# USB_OTG_FS.net
KiCad netlist of a schematic drawn in Altium Designer
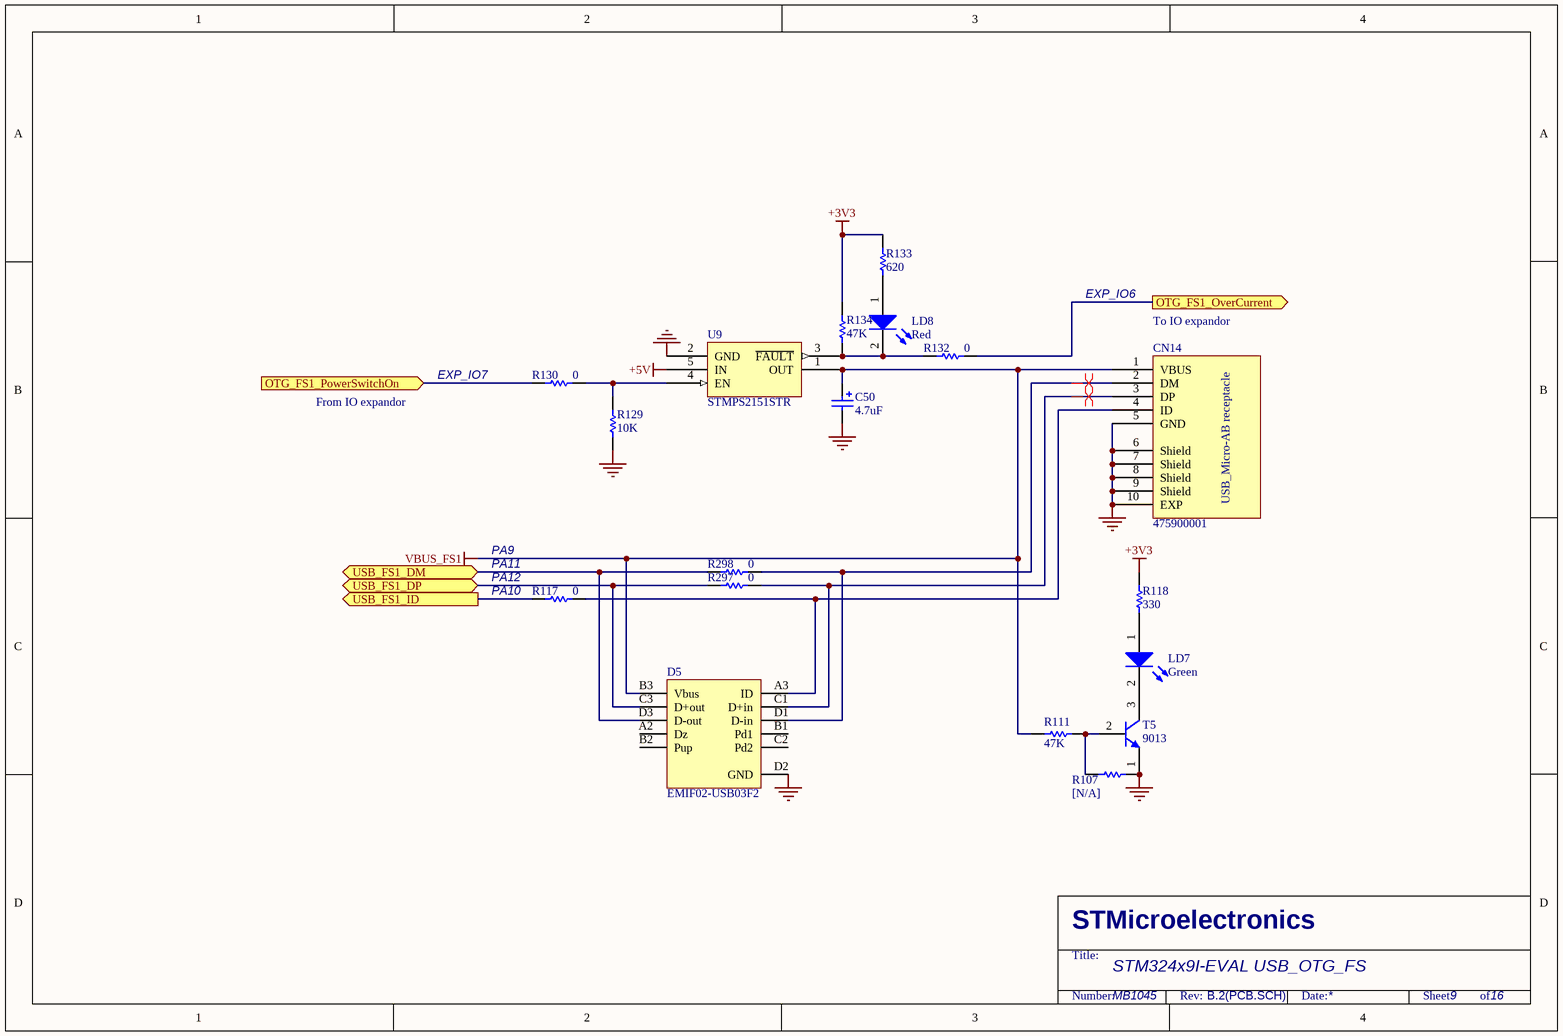
[diagram p0: USB_OTG_FS.SchDoc]

(export (version "E")
  (design (tool "Eeschema 10.0.6"))
  (components
    (comp (ref "C50")
      (value "4.7uF")
      (footprint "TAN-A")
      (description "Polarized Capacitor (Radial)")
      (fields (field (name "PUBLISHER") "Altium Limited"))
      (libsource (lib "Miscellaneous Devices") (part "Cap Pol1"))
    )
    (comp (ref "CN14")
      (value "475900001")
      (footprint "MOLEX_47590001")
      (libsource (lib "mb1045") (part "475900001"))
    )
    (comp (ref "D5")
      (value "EMIF02-USB03F2")
      (footprint "BGA11_0R5_1R57X2R07")
      (libsource (lib "mb1045") (part "EMIF02-USB03F2"))
    )
    (comp (ref "LD7")
      (value "Green")
      (footprint "0603D")
      (description "Typical RED, GREEN, YELLOW, AMBER GaAs LED")
      (fields (field (name "PUBLISHER") "Altium Limited"))
      (libsource (lib "Miscellaneous Devices") (part "LED2"))
    )
    (comp (ref "LD8")
      (value "Red")
      (footprint "0603D")
      (description "Typical RED, GREEN, YELLOW, AMBER GaAs LED")
      (fields (field (name "PUBLISHER") "Altium Limited"))
      (libsource (lib "Miscellaneous Devices") (part "LED2"))
    )
    (comp (ref "R107")
      (value "[N/A]")
      (footprint "0603R")
      (description "Resistor")
      (fields (field (name "PUBLISHER") "Altium Limited"))
      (libsource (lib "Miscellaneous Devices") (part "res1"))
    )
    (comp (ref "R111")
      (value "47K")
      (footprint "0603R")
      (description "Resistor")
      (fields (field (name "PUBLISHER") "Altium Limited"))
      (libsource (lib "Miscellaneous Devices") (part "res1"))
    )
    (comp (ref "R117")
      (value "0")
      (footprint "0603R")
      (description "Resistor")
      (fields (field (name "PUBLISHER") "Altium Limited"))
      (libsource (lib "Miscellaneous Devices") (part "Res1"))
    )
    (comp (ref "R118")
      (value "330")
      (footprint "0603R")
      (description "Resistor")
      (fields (field (name "PUBLISHER") "Altium Limited"))
      (libsource (lib "Miscellaneous Devices") (part "res1"))
    )
    (comp (ref "R129")
      (value "10K")
      (footprint "0603R")
      (description "Resistor")
      (fields (field (name "PUBLISHER") "Altium Limited"))
      (libsource (lib "Miscellaneous Devices") (part "Res1"))
    )
    (comp (ref "R130")
      (value "0")
      (footprint "0603R")
      (description "Resistor")
      (fields (field (name "PUBLISHER") "Altium Limited"))
      (libsource (lib "Miscellaneous Devices") (part "Res1"))
    )
    (comp (ref "R132")
      (value "0")
      (footprint "0603R")
      (description "Resistor")
      (fields (field (name "PUBLISHER") "Altium Limited"))
      (libsource (lib "Miscellaneous Devices") (part "Res1"))
    )
    (comp (ref "R133")
      (value "620")
      (footprint "0603R")
      (description "Resistor")
      (fields (field (name "PUBLISHER") "Altium Limited"))
      (libsource (lib "Miscellaneous Devices") (part "Res1"))
    )
    (comp (ref "R134")
      (value "47K")
      (footprint "0603R")
      (description "Resistor")
      (fields (field (name "PUBLISHER") "Altium Limited"))
      (libsource (lib "Miscellaneous Devices") (part "res1"))
    )
    (comp (ref "R297")
      (value "0")
      (footprint "0603R")
      (description "Resistor")
      (fields (field (name "PUBLISHER") "Altium Limited"))
      (libsource (lib "Miscellaneous Devices") (part "Res1"))
    )
    (comp (ref "R298")
      (value "0")
      (footprint "0603R")
      (description "Resistor")
      (fields (field (name "PUBLISHER") "Altium Limited"))
      (libsource (lib "Miscellaneous Devices") (part "Res1"))
    )
    (comp (ref "T5")
      (value "9013")
      (footprint "SOT23-213")
      (description "NPN Bipolar Transistor")
      (fields (field (name "PUBLISHER") "Altium Limited"))
      (libsource (lib "mb1045") (part "NPN"))
    )
    (comp (ref "U9")
      (value "STMPS2151STR")
      (footprint "SOT23-5")
      (libsource (lib "mb1045") (part "STMPS2141STR"))
    )
  )
  (nets
    (net (code "1") (name "+3V3") (class "Default")
      (node (ref "R118") (pin "2") (pinfunction "2_2") (pintype "passive"))
      (node (ref "R133") (pin "2") (pinfunction "2_2") (pintype "passive"))
      (node (ref "R134") (pin "1") (pinfunction "1_1") (pintype "passive"))
    )
    (net (code "2") (name "+5V") (class "Default")
      (node (ref "U9") (pin "5") (pinfunction "IN_5") (pintype "passive"))
    )
    (net (code "3") (name "/OTG_FS1_OverCurrent") (class "Default")
      (node (ref "R132") (pin "1") (pinfunction "1_1") (pintype "passive"))
    )
    (net (code "4") (name "/OTG_FS1_PowerSwitchOn") (class "Default")
      (node (ref "R130") (pin "2") (pinfunction "2_2") (pintype "passive"))
    )
    (net (code "5") (name "/USB_FS1_DM") (class "Default")
      (node (ref "D5") (pin "D3") (pinfunction "D-out_D3") (pintype "passive"))
      (node (ref "R298") (pin "2") (pinfunction "2_2") (pintype "passive"))
    )
    (net (code "6") (name "/USB_FS1_DP") (class "Default")
      (node (ref "D5") (pin "C3") (pinfunction "D+out_C3") (pintype "passive"))
      (node (ref "R297") (pin "2") (pinfunction "2_2") (pintype "passive"))
    )
    (net (code "7") (name "/USB_FS1_ID") (class "Default")
      (node (ref "R117") (pin "2") (pinfunction "2_2") (pintype "passive"))
    )
    (net (code "8") (name "GND") (class "Default")
      (node (ref "C50") (pin "2") (pinfunction "2_2") (pintype "passive"))
      (node (ref "CN14") (pin "10") (pinfunction "EXP_10") (pintype "passive"))
      (node (ref "CN14") (pin "5") (pinfunction "GND_5") (pintype "passive"))
      (node (ref "CN14") (pin "6") (pinfunction "Shield_6") (pintype "passive"))
      (node (ref "CN14") (pin "7") (pinfunction "Shield_7") (pintype "passive"))
      (node (ref "CN14") (pin "8") (pinfunction "Shield_8") (pintype "passive"))
      (node (ref "CN14") (pin "9") (pinfunction "Shield_9") (pintype "passive"))
      (node (ref "D5") (pin "D2") (pinfunction "GND_D2") (pintype "passive"))
      (node (ref "R107") (pin "1") (pinfunction "1_1") (pintype "passive"))
      (node (ref "R129") (pin "1") (pinfunction "1_1") (pintype "passive"))
      (node (ref "T5") (pin "1") (pinfunction "E_1") (pintype "passive"))
      (node (ref "U9") (pin "2") (pinfunction "GND_2") (pintype "passive"))
    )
    (net (code "9") (name "Net-(CN14-DM)") (class "Default")
      (node (ref "CN14") (pin "2") (pinfunction "DM_2") (pintype "passive"))
      (node (ref "D5") (pin "D1") (pinfunction "D-in_D1") (pintype "passive"))
      (node (ref "R298") (pin "1") (pinfunction "1_1") (pintype "passive"))
    )
    (net (code "10") (name "Net-(CN14-DP)") (class "Default")
      (node (ref "CN14") (pin "3") (pinfunction "DP_3") (pintype "passive"))
      (node (ref "D5") (pin "C1") (pinfunction "D+in_C1") (pintype "passive"))
      (node (ref "R297") (pin "1") (pinfunction "1_1") (pintype "passive"))
    )
    (net (code "11") (name "Net-(CN14-ID)") (class "Default")
      (node (ref "CN14") (pin "4") (pinfunction "ID_4") (pintype "passive"))
      (node (ref "D5") (pin "A3") (pinfunction "ID_A3") (pintype "passive"))
      (node (ref "R117") (pin "1") (pinfunction "1_1") (pintype "passive"))
    )
    (net (code "12") (name "Net-(LD7-A)") (class "Default")
      (node (ref "LD7") (pin "1") (pinfunction "A_1") (pintype "passive"))
      (node (ref "R118") (pin "1") (pinfunction "1_1") (pintype "passive"))
    )
    (net (code "13") (name "Net-(LD7-K)") (class "Default")
      (node (ref "LD7") (pin "2") (pinfunction "K_2") (pintype "passive"))
      (node (ref "T5") (pin "3") (pinfunction "C_3") (pintype "passive"))
    )
    (net (code "14") (name "Net-(LD8-A)") (class "Default")
      (node (ref "LD8") (pin "1") (pinfunction "A_1") (pintype "passive"))
      (node (ref "R133") (pin "1") (pinfunction "1_1") (pintype "passive"))
    )
    (net (code "15") (name "Net-(LD8-K)") (class "Default")
      (node (ref "LD8") (pin "2") (pinfunction "K_2") (pintype "passive"))
      (node (ref "R132") (pin "2") (pinfunction "2_2") (pintype "passive"))
      (node (ref "R134") (pin "2") (pinfunction "2_2") (pintype "passive"))
      (node (ref "U9") (pin "3") (pinfunction "~{FAULT}_3") (pintype "output"))
    )
    (net (code "16") (name "Net-(T5-B)") (class "Default")
      (node (ref "R107") (pin "2") (pinfunction "2_2") (pintype "passive"))
      (node (ref "R111") (pin "2") (pinfunction "2_2") (pintype "passive"))
      (node (ref "T5") (pin "2") (pinfunction "B_2") (pintype "passive"))
    )
    (net (code "17") (name "Net-(U9-EN)") (class "Default")
      (node (ref "R129") (pin "2") (pinfunction "2_2") (pintype "passive"))
      (node (ref "R130") (pin "1") (pinfunction "1_1") (pintype "passive"))
      (node (ref "U9") (pin "4") (pinfunction "EN_4") (pintype "input"))
    )
    (net (code "18") (name "VBUS_FS1") (class "Default")
      (node (ref "C50") (pin "1") (pinfunction "1_1") (pintype "passive"))
      (node (ref "CN14") (pin "1") (pinfunction "VBUS_1") (pintype "passive"))
      (node (ref "D5") (pin "B3") (pinfunction "Vbus_B3") (pintype "passive"))
      (node (ref "R111") (pin "1") (pinfunction "1_1") (pintype "passive"))
      (node (ref "U9") (pin "1") (pinfunction "OUT_1") (pintype "passive"))
    )
    (net (code "19") (name "unconnected-(D5-Dz-PadA2)") (class "Default")
      (node (ref "D5") (pin "A2") (pinfunction "Dz_A2") (pintype "passive"))
    )
    (net (code "20") (name "unconnected-(D5-Pd1-PadB1)") (class "Default")
      (node (ref "D5") (pin "B1") (pinfunction "Pd1_B1") (pintype "passive"))
    )
    (net (code "21") (name "unconnected-(D5-Pd2-PadC2)") (class "Default")
      (node (ref "D5") (pin "C2") (pinfunction "Pd2_C2") (pintype "passive"))
    )
    (net (code "22") (name "unconnected-(D5-Pup-PadB2)") (class "Default")
      (node (ref "D5") (pin "B2") (pinfunction "Pup_B2") (pintype "passive"))
    )
  )
)
